# AIM2_-_ADCS_REVB_save.net
KiCad netlist of a schematic drawn in Altium Designer
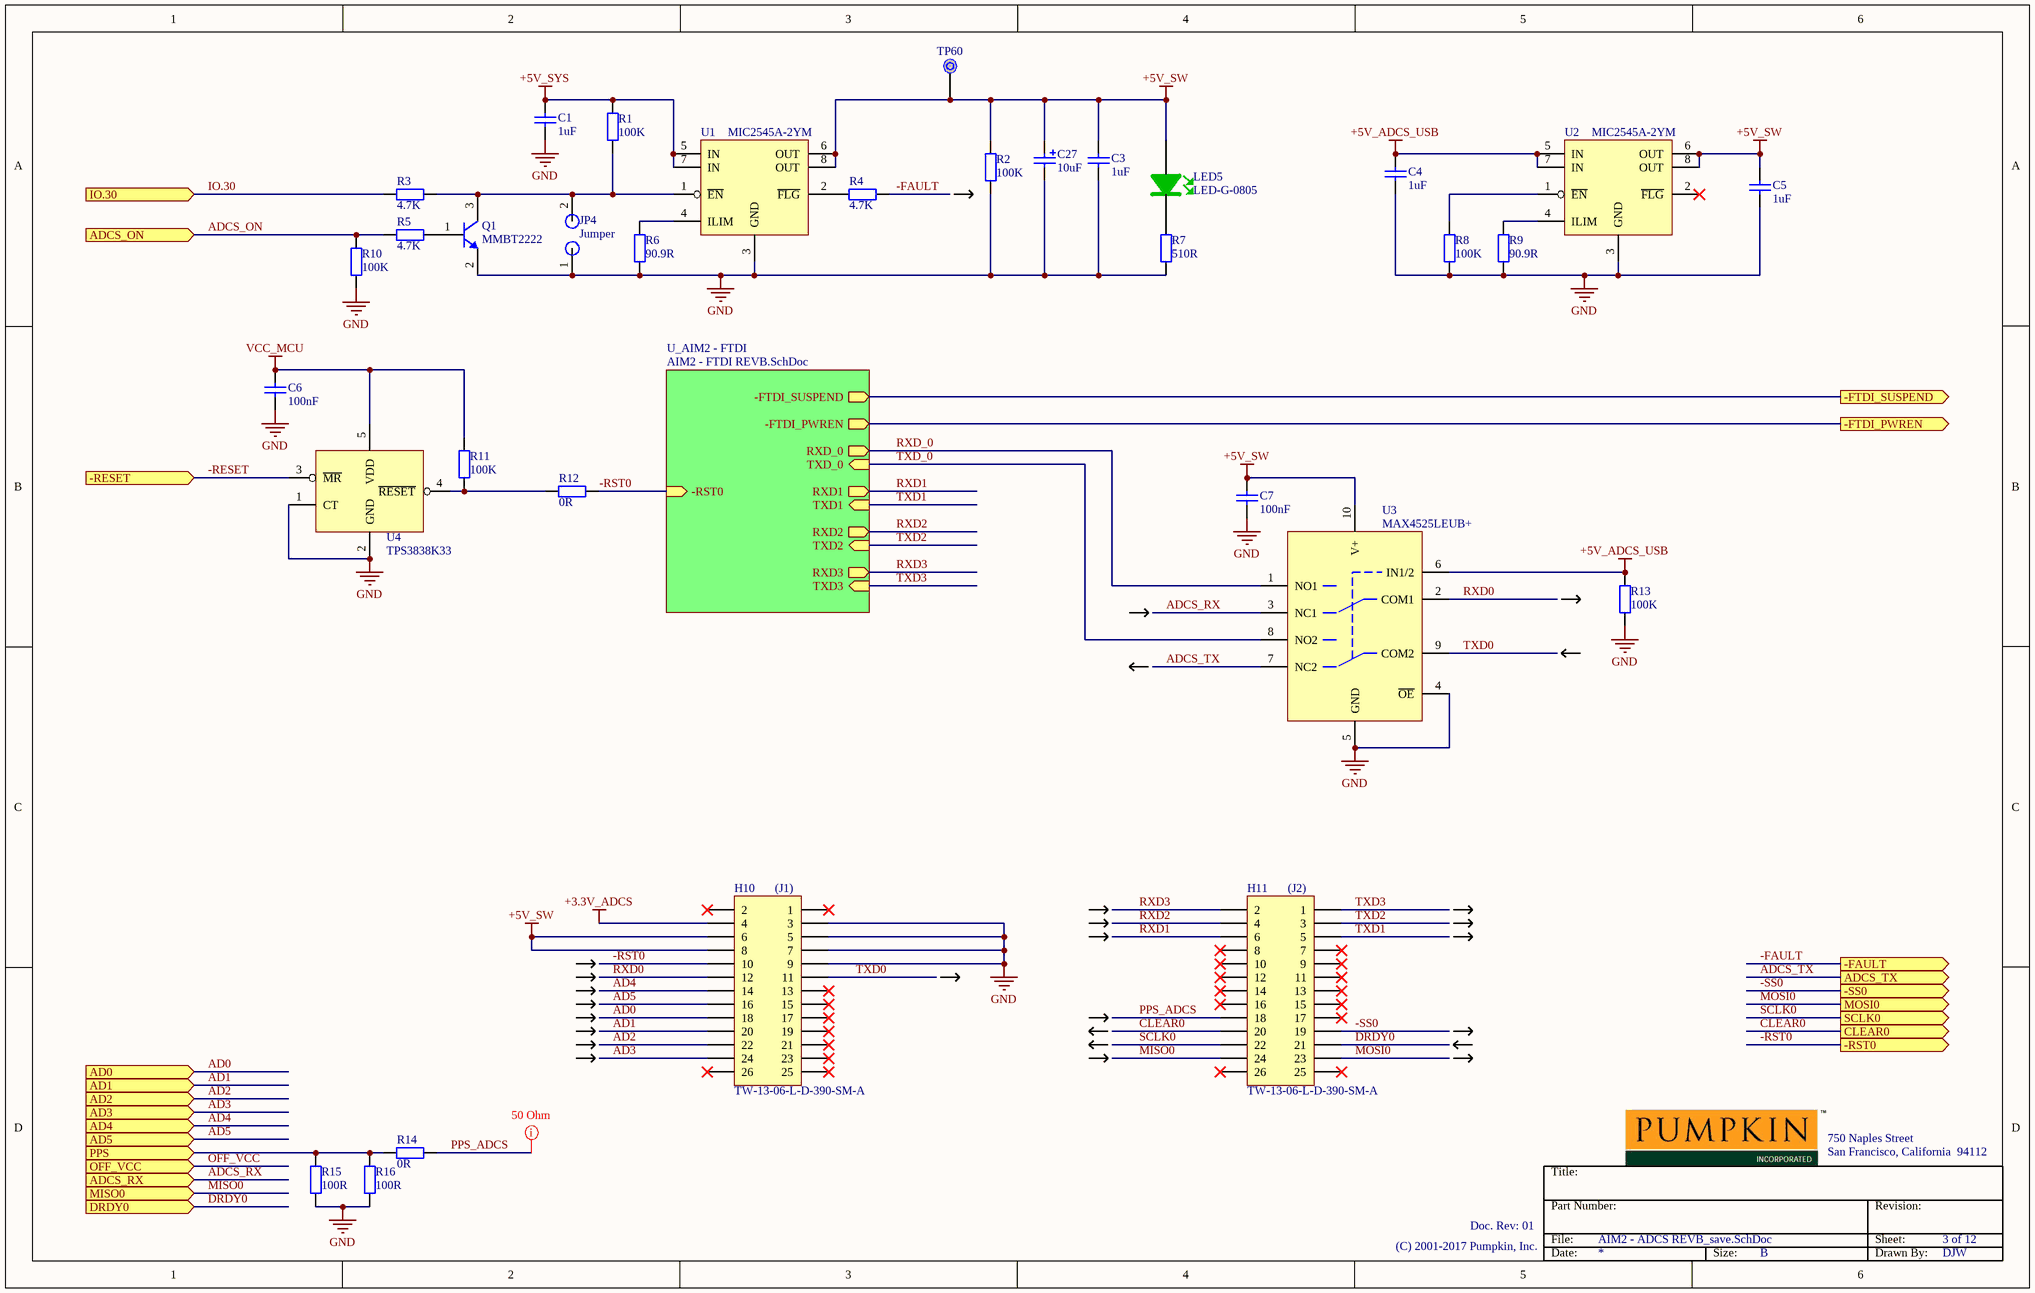
[diagram p0: AIM2 - ADCS REVB_save.SchDoc]

(export (version "E")
  (design (tool "Eeschema 10.0.6"))
  (components
    (comp (ref "C1")
      (value "1uF")
      (footprint "0805 CAP")
      (description "Capacitor 1uF 0805 X7R 25V 10%")
      (libsource (lib "Supernova passives") (part "Capacitor 1uF 0805"))
    )
    (comp (ref "C3")
      (value "1uF")
      (footprint "0805 CAP")
      (description "Capacitor 1uF 0805 X7R 25V 10%")
      (libsource (lib "Supernova passives") (part "Capacitor 1uF 0805"))
    )
    (comp (ref "C4")
      (value "1uF")
      (footprint "0805 CAP")
      (description "Capacitor 1uF 0805 X7R 25V 10%")
      (libsource (lib "Supernova passives") (part "Capacitor 1uF 0805"))
    )
    (comp (ref "C5")
      (value "1uF")
      (footprint "0805 CAP")
      (description "Capacitor 1uF 0805 X7R 25V 10%")
      (libsource (lib "Supernova passives") (part "Capacitor 1uF 0805"))
    )
    (comp (ref "C6")
      (value "100nF")
      (footprint "0603 CAP")
      (description "Capacitor 100nF 0603 X7R 50V 5%")
      (libsource (lib "Supernova passives") (part "Capacitor 100nF 0603"))
    )
    (comp (ref "C7")
      (value "100nF")
      (footprint "0603 CAP")
      (description "Capacitor 100nF 0603 X7R 50V 5%")
      (libsource (lib "Supernova passives") (part "Capacitor 100nF 0603"))
    )
    (comp (ref "C27")
      (value "10uF")
      (footprint "6032 POLAR CAP")
      (description "Capacitor 10uF 6032 TANT 16V 10%")
      (libsource (lib "Supernova passives") (part "Capacitor 10uF 6032 Tantalum"))
    )
    (comp (ref "H10")
      (value "TW-13-06-L-D-390-SM-A")
      (footprint "TW-13-06-X-D-390-SM-A")
      (description "Header 13x2 TH 2mm pitch")
      (libsource (lib "Supernova") (part "TW-13-06-L-D-390-SM-A"))
    )
    (comp (ref "H11")
      (value "TW-13-06-L-D-390-SM-A")
      (footprint "TW-13-06-X-D-390-SM-A")
      (description "Header 13x2 TH 2mm pitch")
      (libsource (lib "Supernova") (part "TW-13-06-L-D-390-SM-A"))
    )
    (comp (ref "JP4")
      (value "Jumper")
      (footprint "0805 RES 1 way jumper")
      (description "Jumper 0805 1 pos")
      (libsource (lib "Supernova passives") (part "Jumper 1 way 0805"))
    )
    (comp (ref "LED5")
      (value "LED-G-0805")
      (footprint "0805 LED-GREEN")
      (description "LED Green 0805")
      (libsource (lib "Supernova passives") (part "LED GREEN 0805"))
    )
    (comp (ref "Q1")
      (value "MMBT2222")
      (footprint "SOT23-3")
      (description "Transistor NPN")
      (libsource (lib "Supernova") (part "MMBT2222ALT1GOSCT-ND"))
    )
    (comp (ref "R1")
      (value "100K")
      (footprint "0805 RES")
      (description "Resistor 100K 0805 0.5W 1%")
      (libsource (lib "Supernova passives") (part "Resistor 100K 0805"))
    )
    (comp (ref "R2")
      (value "100K")
      (footprint "0805 RES")
      (description "Resistor 100K 0805 0.5W 1%")
      (libsource (lib "Supernova passives") (part "Resistor 100K 0805"))
    )
    (comp (ref "R3")
      (value "4.7K")
      (footprint "0805 RES")
      (description "Resistor 4.7K 0805 0.125W 1%")
      (libsource (lib "Supernova passives") (part "Resistor 4K7 0805"))
    )
    (comp (ref "R4")
      (value "4.7K")
      (footprint "0805 RES")
      (description "Resistor 4.7K 0805 0.125W 1%")
      (libsource (lib "Supernova passives") (part "Resistor 4K7 0805"))
    )
    (comp (ref "R5")
      (value "4.7K")
      (footprint "0805 RES")
      (description "Resistor 4.7K 0805 0.125W 1%")
      (libsource (lib "Supernova passives") (part "Resistor 4K7 0805"))
    )
    (comp (ref "R6")
      (value "90.9R")
      (footprint "0805 RES")
      (description "Resistor 90.9R 0805 0.125W 1%")
      (libsource (lib "Supernova passives") (part "Resistor 90R9 0805"))
    )
    (comp (ref "R7")
      (value "510R")
      (footprint "0805 RES")
      (description "Resistor 470K 0805 0.125W 1%")
      (libsource (lib "Supernova passives") (part "Resistor 510R 0805"))
    )
    (comp (ref "R8")
      (value "100K")
      (footprint "0805 RES")
      (description "Resistor 100K 0805 0.5W 1%")
      (libsource (lib "Supernova passives") (part "Resistor 100K 0805"))
    )
    (comp (ref "R9")
      (value "90.9R")
      (footprint "0805 RES")
      (description "Resistor 90.9R 0805 0.125W 1%")
      (libsource (lib "Supernova passives") (part "Resistor 90R9 0805"))
    )
    (comp (ref "R10")
      (value "100K")
      (footprint "0805 RES")
      (description "Resistor 100K 0805 0.5W 1%")
      (libsource (lib "Supernova passives") (part "Resistor 100K 0805"))
    )
    (comp (ref "R11")
      (value "100K")
      (footprint "0805 RES")
      (description "Resistor 100K 0805 0.5W 1%")
      (libsource (lib "Supernova passives") (part "Resistor 100K 0805"))
    )
    (comp (ref "R12")
      (value "0R")
      (footprint "0805 RES")
      (description "Resistor 0R 0805 0.125W")
      (libsource (lib "Supernova passives") (part "Resistor 0R 0805"))
    )
    (comp (ref "R13")
      (value "100K")
      (footprint "0805 RES")
      (description "Resistor 100K 0805 0.5W 1%")
      (libsource (lib "Supernova passives") (part "Resistor 100K 0805"))
    )
    (comp (ref "R14")
      (value "0R")
      (footprint "0805 RES")
      (description "Resistor 0R 0805 0.125W")
      (libsource (lib "Supernova passives") (part "Resistor 0R 0805"))
    )
    (comp (ref "R15")
      (value "100R")
      (footprint "0805 RES")
      (description "Resistor 100R 0805 0.125W 1%")
      (libsource (lib "Supernova passives") (part "Resistor 100R 0805"))
    )
    (comp (ref "R16")
      (value "100R")
      (footprint "0805 RES")
      (description "Resistor 100R 0805 0.125W 1%")
      (libsource (lib "Supernova passives") (part "Resistor 100R 0805"))
    )
    (comp (ref "TP60")
      (value "Testpoint")
      (footprint "Testpoint")
      (libsource (lib "Supernova") (part "Testpoint"))
    )
    (comp (ref "U1")
      (value "MIC2545A-2YM")
      (footprint "SOIC-8")
      (description "IC Current Limiter")
      (libsource (lib "Supernova") (part "MIC2545A-2YM"))
    )
    (comp (ref "U2")
      (value "MIC2545A-2YM")
      (footprint "SOIC-8")
      (description "IC Current Limiter")
      (libsource (lib "Supernova") (part "MIC2545A-2YM"))
    )
    (comp (ref "U3")
      (value "MAX4525LEUB+")
      (footprint "MSOP-10")
      (description "IC Analog Switch DPDT")
      (libsource (lib "Supernova") (part "MAX4525LEUB+"))
    )
    (comp (ref "U4")
      (value "TPS3838K33")
      (footprint "SOT23-5")
      (description "IC Supervisor Reset")
      (libsource (lib "Supernova") (part "TPS3838K33DBVR"))
    )
  )
  (nets
    (net (code "1") (name "+3.3V_ADCS") (class "Default")
      (node (ref "H10") (pin "4") (pinfunction "4_4") (pintype "passive"))
    )
    (net (code "2") (name "+5V_ADCS_USB") (class "Default")
      (node (ref "C4") (pin "2") (pinfunction "2_2") (pintype "passive"))
      (node (ref "R13") (pin "2") (pinfunction "2_2") (pintype "passive"))
      (node (ref "U2") (pin "5") (pinfunction "IN_5") (pintype "passive"))
      (node (ref "U2") (pin "7") (pinfunction "IN_7") (pintype "passive"))
      (node (ref "U3") (pin "6") (pinfunction "IN1/2_6") (pintype "passive"))
    )
    (net (code "3") (name "+5V_SW") (class "Default")
      (node (ref "C27") (pin "1") (pinfunction "1_1") (pintype "passive"))
      (node (ref "C3") (pin "2") (pinfunction "2_2") (pintype "passive"))
      (node (ref "C5") (pin "2") (pinfunction "2_2") (pintype "passive"))
      (node (ref "C7") (pin "2") (pinfunction "2_2") (pintype "passive"))
      (node (ref "H10") (pin "6") (pinfunction "6_6") (pintype "passive"))
      (node (ref "H10") (pin "8") (pinfunction "8_8") (pintype "passive"))
      (node (ref "LED5") (pin "2") (pinfunction "2_2") (pintype "passive"))
      (node (ref "R2") (pin "2") (pinfunction "2_2") (pintype "passive"))
      (node (ref "TP60") (pin "1") (pinfunction "1_1") (pintype "passive"))
      (node (ref "U1") (pin "6") (pinfunction "OUT_6") (pintype "passive"))
      (node (ref "U1") (pin "8") (pinfunction "OUT_8") (pintype "passive"))
      (node (ref "U2") (pin "6") (pinfunction "OUT_6") (pintype "passive"))
      (node (ref "U2") (pin "8") (pinfunction "OUT_8") (pintype "passive"))
      (node (ref "U3") (pin "10") (pinfunction "V+_10") (pintype "passive"))
    )
    (net (code "4") (name "+5V_SYS") (class "Default")
      (node (ref "C1") (pin "2") (pinfunction "2_2") (pintype "passive"))
      (node (ref "R1") (pin "2") (pinfunction "2_2") (pintype "passive"))
      (node (ref "U1") (pin "5") (pinfunction "IN_5") (pintype "passive"))
      (node (ref "U1") (pin "7") (pinfunction "IN_7") (pintype "passive"))
    )
    (net (code "5") (name "/-FAULT") (class "Default")
      (node (ref "R4") (pin "2") (pinfunction "2_2") (pintype "passive"))
    )
    (net (code "8") (name "/-RESET") (class "Default")
      (node (ref "U4") (pin "3") (pinfunction "~{MR}_3") (pintype "passive"))
    )
    (net (code "9") (name "/-RST0") (class "Default")
      (node (ref "H10") (pin "10") (pinfunction "10_10") (pintype "passive"))
      (node (ref "R12") (pin "2") (pinfunction "2_2") (pintype "passive"))
    )
    (net (code "10") (name "/-SS0") (class "Default")
      (node (ref "H11") (pin "19") (pinfunction "19_19") (pintype "passive"))
    )
    (net (code "11") (name "/AD0") (class "Default")
      (node (ref "H10") (pin "18") (pinfunction "18_18") (pintype "passive"))
    )
    (net (code "12") (name "/AD1") (class "Default")
      (node (ref "H10") (pin "20") (pinfunction "20_20") (pintype "passive"))
    )
    (net (code "13") (name "/AD2") (class "Default")
      (node (ref "H10") (pin "22") (pinfunction "22_22") (pintype "passive"))
    )
    (net (code "14") (name "/AD3") (class "Default")
      (node (ref "H10") (pin "24") (pinfunction "24_24") (pintype "passive"))
    )
    (net (code "15") (name "/AD4") (class "Default")
      (node (ref "H10") (pin "14") (pinfunction "14_14") (pintype "passive"))
    )
    (net (code "16") (name "/AD5") (class "Default")
      (node (ref "H10") (pin "16") (pinfunction "16_16") (pintype "passive"))
    )
    (net (code "17") (name "/ADCS_ON") (class "Default")
      (node (ref "R10") (pin "2") (pinfunction "2_2") (pintype "passive"))
      (node (ref "R5") (pin "1") (pinfunction "1_1") (pintype "passive"))
    )
    (net (code "18") (name "/ADCS_RX") (class "Default")
      (node (ref "U3") (pin "3") (pinfunction "NC1_3") (pintype "passive"))
    )
    (net (code "19") (name "/ADCS_TX") (class "Default")
      (node (ref "U3") (pin "7") (pinfunction "NC2_7") (pintype "passive"))
    )
    (net (code "20") (name "/CLEAR0") (class "Default")
      (node (ref "H11") (pin "20") (pinfunction "20_20") (pintype "passive"))
    )
    (net (code "21") (name "/DRDY0") (class "Default")
      (node (ref "H11") (pin "21") (pinfunction "21_21") (pintype "passive"))
    )
    (net (code "22") (name "/IO.30") (class "Default")
      (node (ref "R3") (pin "1") (pinfunction "1_1") (pintype "passive"))
    )
    (net (code "23") (name "/MISO0") (class "Default")
      (node (ref "H11") (pin "24") (pinfunction "24_24") (pintype "passive"))
    )
    (net (code "24") (name "/MOSI0") (class "Default")
      (node (ref "H11") (pin "23") (pinfunction "23_23") (pintype "passive"))
    )
    (net (code "26") (name "/PPS") (class "Default")
      (node (ref "R14") (pin "1") (pinfunction "1_1") (pintype "passive"))
      (node (ref "R15") (pin "2") (pinfunction "2_2") (pintype "passive"))
      (node (ref "R16") (pin "2") (pinfunction "2_2") (pintype "passive"))
    )
    (net (code "27") (name "/PPS_ADCS") (class "Default")
      (node (ref "H11") (pin "18") (pinfunction "18_18") (pintype "passive"))
      (node (ref "R14") (pin "2") (pinfunction "2_2") (pintype "passive"))
    )
    (net (code "28") (name "/RXD0") (class "Default")
      (node (ref "H10") (pin "12") (pinfunction "12_12") (pintype "passive"))
      (node (ref "U3") (pin "2") (pinfunction "COM1_2") (pintype "passive"))
    )
    (net (code "29") (name "/RXD1") (class "Default")
      (node (ref "H11") (pin "6") (pinfunction "6_6") (pintype "passive"))
    )
    (net (code "30") (name "/RXD2") (class "Default")
      (node (ref "H11") (pin "4") (pinfunction "4_4") (pintype "passive"))
    )
    (net (code "31") (name "/RXD3") (class "Default")
      (node (ref "H11") (pin "2") (pinfunction "2_2") (pintype "passive"))
    )
    (net (code "32") (name "/RXD_0") (class "Default")
      (node (ref "U3") (pin "1") (pinfunction "NO1_1") (pintype "passive"))
    )
    (net (code "33") (name "/SCLK0") (class "Default")
      (node (ref "H11") (pin "22") (pinfunction "22_22") (pintype "passive"))
    )
    (net (code "34") (name "/TXD0") (class "Default")
      (node (ref "H10") (pin "11") (pinfunction "11_11") (pintype "passive"))
      (node (ref "U3") (pin "9") (pinfunction "COM2_9") (pintype "passive"))
    )
    (net (code "35") (name "/TXD1") (class "Default")
      (node (ref "H11") (pin "5") (pinfunction "5_5") (pintype "passive"))
    )
    (net (code "36") (name "/TXD2") (class "Default")
      (node (ref "H11") (pin "3") (pinfunction "3_3") (pintype "passive"))
    )
    (net (code "37") (name "/TXD3") (class "Default")
      (node (ref "H11") (pin "1") (pinfunction "1_1") (pintype "passive"))
    )
    (net (code "38") (name "/TXD_0") (class "Default")
      (node (ref "U3") (pin "8") (pinfunction "NO2_8") (pintype "passive"))
    )
    (net (code "39") (name "GND") (class "Default")
      (node (ref "C1") (pin "1") (pinfunction "1_1") (pintype "passive"))
      (node (ref "C27") (pin "2") (pinfunction "2_2") (pintype "passive"))
      (node (ref "C3") (pin "1") (pinfunction "1_1") (pintype "passive"))
      (node (ref "C4") (pin "1") (pinfunction "1_1") (pintype "passive"))
      (node (ref "C5") (pin "1") (pinfunction "1_1") (pintype "passive"))
      (node (ref "C6") (pin "1") (pinfunction "1_1") (pintype "passive"))
      (node (ref "C7") (pin "1") (pinfunction "1_1") (pintype "passive"))
      (node (ref "H10") (pin "3") (pinfunction "3_3") (pintype "passive"))
      (node (ref "H10") (pin "5") (pinfunction "5_5") (pintype "passive"))
      (node (ref "H10") (pin "7") (pinfunction "7_7") (pintype "passive"))
      (node (ref "H10") (pin "9") (pinfunction "9_9") (pintype "passive"))
      (node (ref "JP4") (pin "1") (pinfunction "5_1") (pintype "passive"))
      (node (ref "Q1") (pin "2") (pinfunction "E_2") (pintype "passive"))
      (node (ref "R10") (pin "1") (pinfunction "1_1") (pintype "passive"))
      (node (ref "R13") (pin "1") (pinfunction "1_1") (pintype "passive"))
      (node (ref "R15") (pin "1") (pinfunction "1_1") (pintype "passive"))
      (node (ref "R16") (pin "1") (pinfunction "1_1") (pintype "passive"))
      (node (ref "R2") (pin "1") (pinfunction "1_1") (pintype "passive"))
      (node (ref "R6") (pin "1") (pinfunction "1_1") (pintype "passive"))
      (node (ref "R7") (pin "1") (pinfunction "1_1") (pintype "passive"))
      (node (ref "R8") (pin "1") (pinfunction "1_1") (pintype "passive"))
      (node (ref "R9") (pin "1") (pinfunction "1_1") (pintype "passive"))
      (node (ref "U1") (pin "3") (pinfunction "GND_3") (pintype "passive"))
      (node (ref "U2") (pin "3") (pinfunction "GND_3") (pintype "passive"))
      (node (ref "U3") (pin "4") (pinfunction "~{OE}_4") (pintype "passive"))
      (node (ref "U3") (pin "5") (pinfunction "GND_5") (pintype "passive"))
      (node (ref "U4") (pin "1") (pinfunction "CT_1") (pintype "passive"))
      (node (ref "U4") (pin "2") (pinfunction "GND_2") (pintype "passive"))
    )
    (net (code "40") (name "Net-(LED5-Pad1)") (class "Default")
      (node (ref "LED5") (pin "1") (pinfunction "1_1") (pintype "passive"))
      (node (ref "R7") (pin "2") (pinfunction "2_2") (pintype "passive"))
    )
    (net (code "41") (name "Net-(Q1-B)") (class "Default")
      (node (ref "Q1") (pin "1") (pinfunction "B_1") (pintype "passive"))
      (node (ref "R5") (pin "2") (pinfunction "2_2") (pintype "passive"))
    )
    (net (code "42") (name "Net-(Q1-C)") (class "Default")
      (node (ref "JP4") (pin "2") (pinfunction "5_2") (pintype "passive"))
      (node (ref "Q1") (pin "3") (pinfunction "C_3") (pintype "passive"))
      (node (ref "R1") (pin "1") (pinfunction "1_1") (pintype "passive"))
      (node (ref "R3") (pin "2") (pinfunction "2_2") (pintype "passive"))
      (node (ref "U1") (pin "1") (pinfunction "~{EN}_1") (pintype "passive"))
    )
    (net (code "43") (name "Net-(U1-ILIM)") (class "Default")
      (node (ref "R6") (pin "2") (pinfunction "2_2") (pintype "passive"))
      (node (ref "U1") (pin "4") (pinfunction "ILIM_4") (pintype "passive"))
    )
    (net (code "44") (name "Net-(U1-~{FLG})") (class "Default")
      (node (ref "R4") (pin "1") (pinfunction "1_1") (pintype "passive"))
      (node (ref "U1") (pin "2") (pinfunction "~{FLG}_2") (pintype "passive"))
    )
    (net (code "45") (name "Net-(U2-ILIM)") (class "Default")
      (node (ref "R9") (pin "2") (pinfunction "2_2") (pintype "passive"))
      (node (ref "U2") (pin "4") (pinfunction "ILIM_4") (pintype "passive"))
    )
    (net (code "46") (name "Net-(U2-~{EN})") (class "Default")
      (node (ref "R8") (pin "2") (pinfunction "2_2") (pintype "passive"))
      (node (ref "U2") (pin "1") (pinfunction "~{EN}_1") (pintype "passive"))
    )
    (net (code "47") (name "Net-(U4-~{RESET})") (class "Default")
      (node (ref "R11") (pin "1") (pinfunction "1_1") (pintype "passive"))
      (node (ref "R12") (pin "1") (pinfunction "1_1") (pintype "passive"))
      (node (ref "U4") (pin "4") (pinfunction "~{RESET}_4") (pintype "passive"))
    )
    (net (code "48") (name "VCC_MCU") (class "Default")
      (node (ref "C6") (pin "2") (pinfunction "2_2") (pintype "passive"))
      (node (ref "R11") (pin "2") (pinfunction "2_2") (pintype "passive"))
      (node (ref "U4") (pin "5") (pinfunction "VDD_5") (pintype "passive"))
    )
    (net (code "49") (name "unconnected-(H10-Pad1)") (class "Default")
      (node (ref "H10") (pin "1") (pinfunction "1_1") (pintype "passive+no_connect"))
    )
    (net (code "50") (name "unconnected-(H10-Pad2)") (class "Default")
      (node (ref "H10") (pin "2") (pinfunction "2_2") (pintype "passive+no_connect"))
    )
    (net (code "51") (name "unconnected-(H10-Pad13)") (class "Default")
      (node (ref "H10") (pin "13") (pinfunction "13_13") (pintype "passive+no_connect"))
    )
    (net (code "52") (name "unconnected-(H10-Pad15)") (class "Default")
      (node (ref "H10") (pin "15") (pinfunction "15_15") (pintype "passive+no_connect"))
    )
    (net (code "53") (name "unconnected-(H10-Pad17)") (class "Default")
      (node (ref "H10") (pin "17") (pinfunction "17_17") (pintype "passive+no_connect"))
    )
    (net (code "54") (name "unconnected-(H10-Pad19)") (class "Default")
      (node (ref "H10") (pin "19") (pinfunction "19_19") (pintype "passive+no_connect"))
    )
    (net (code "55") (name "unconnected-(H10-Pad21)") (class "Default")
      (node (ref "H10") (pin "21") (pinfunction "21_21") (pintype "passive+no_connect"))
    )
    (net (code "56") (name "unconnected-(H10-Pad23)") (class "Default")
      (node (ref "H10") (pin "23") (pinfunction "23_23") (pintype "passive+no_connect"))
    )
    (net (code "57") (name "unconnected-(H10-Pad25)") (class "Default")
      (node (ref "H10") (pin "25") (pinfunction "25_25") (pintype "passive+no_connect"))
    )
    (net (code "58") (name "unconnected-(H10-Pad26)") (class "Default")
      (node (ref "H10") (pin "26") (pinfunction "26_26") (pintype "passive+no_connect"))
    )
    (net (code "59") (name "unconnected-(H11-Pad7)") (class "Default")
      (node (ref "H11") (pin "7") (pinfunction "7_7") (pintype "passive+no_connect"))
    )
    (net (code "60") (name "unconnected-(H11-Pad8)") (class "Default")
      (node (ref "H11") (pin "8") (pinfunction "8_8") (pintype "passive+no_connect"))
    )
    (net (code "61") (name "unconnected-(H11-Pad9)") (class "Default")
      (node (ref "H11") (pin "9") (pinfunction "9_9") (pintype "passive+no_connect"))
    )
    (net (code "62") (name "unconnected-(H11-Pad10)") (class "Default")
      (node (ref "H11") (pin "10") (pinfunction "10_10") (pintype "passive+no_connect"))
    )
    (net (code "63") (name "unconnected-(H11-Pad11)") (class "Default")
      (node (ref "H11") (pin "11") (pinfunction "11_11") (pintype "passive+no_connect"))
    )
    (net (code "64") (name "unconnected-(H11-Pad12)") (class "Default")
      (node (ref "H11") (pin "12") (pinfunction "12_12") (pintype "passive+no_connect"))
    )
    (net (code "65") (name "unconnected-(H11-Pad13)") (class "Default")
      (node (ref "H11") (pin "13") (pinfunction "13_13") (pintype "passive+no_connect"))
    )
    (net (code "66") (name "unconnected-(H11-Pad14)") (class "Default")
      (node (ref "H11") (pin "14") (pinfunction "14_14") (pintype "passive+no_connect"))
    )
    (net (code "67") (name "unconnected-(H11-Pad15)") (class "Default")
      (node (ref "H11") (pin "15") (pinfunction "15_15") (pintype "passive+no_connect"))
    )
    (net (code "68") (name "unconnected-(H11-Pad16)") (class "Default")
      (node (ref "H11") (pin "16") (pinfunction "16_16") (pintype "passive+no_connect"))
    )
    (net (code "69") (name "unconnected-(H11-Pad17)") (class "Default")
      (node (ref "H11") (pin "17") (pinfunction "17_17") (pintype "passive+no_connect"))
    )
    (net (code "70") (name "unconnected-(H11-Pad25)") (class "Default")
      (node (ref "H11") (pin "25") (pinfunction "25_25") (pintype "passive+no_connect"))
    )
    (net (code "71") (name "unconnected-(H11-Pad26)") (class "Default")
      (node (ref "H11") (pin "26") (pinfunction "26_26") (pintype "passive+no_connect"))
    )
    (net (code "72") (name "unconnected-(U2-~{FLG}-Pad2)") (class "Default")
      (node (ref "U2") (pin "2") (pinfunction "~{FLG}_2") (pintype "passive+no_connect"))
    )
  )
)
